# 03_-_AMG.net
KiCad netlist of a schematic drawn in Altium Designer
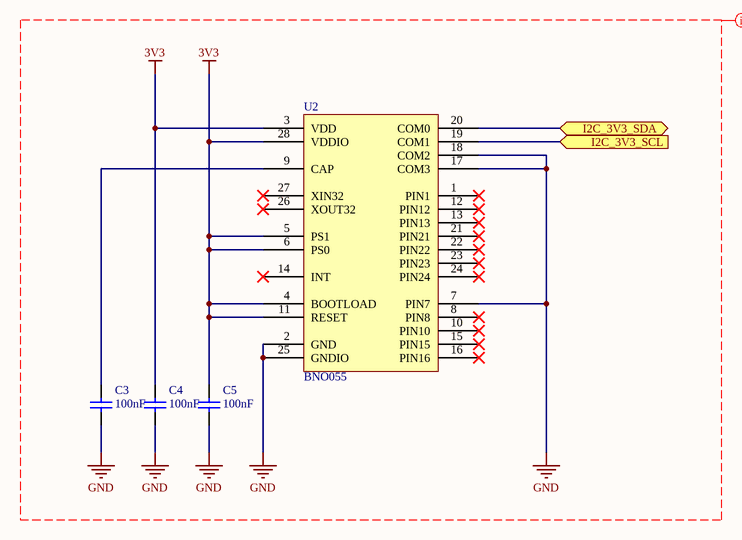
[diagram p0: [03] - AMG.SchDoc]

(export (version "E")
  (design (tool "Eeschema 10.0.6"))
  (components
    (comp (ref "C3")
      (value "100nF")
      (footprint "CAPC0603(1608)100_L")
      (description "CAP 100nF 50V ±10% 0603 (1608 Metric) Thickness 1mm SMD")
      (fields
        (field (name "TOLERANCE") "±10%")
        (field (name "MANUFACTURER PART NUMBER") "C0603C104K5RACAUTO")
      )
      (libsource (lib "Altium Content Vault") (part "CMP-1035-02592-1"))
    )
    (comp (ref "C4")
      (value "100nF")
      (footprint "CAPC0603(1608)100_L")
      (description "CAP 100nF 50V ±10% 0603 (1608 Metric) Thickness 1mm SMD")
      (fields
        (field (name "TOLERANCE") "±10%")
        (field (name "MANUFACTURER PART NUMBER") "C0603C104K5RACAUTO")
      )
      (libsource (lib "Altium Content Vault") (part "CMP-1035-02592-1"))
    )
    (comp (ref "C5")
      (value "100nF")
      (footprint "CAPC0603(1608)100_L")
      (description "CAP 100nF 50V ±10% 0603 (1608 Metric) Thickness 1mm SMD")
      (fields
        (field (name "TOLERANCE") "±10%")
        (field (name "MANUFACTURER PART NUMBER") "C0603C104K5RACAUTO")
      )
      (libsource (lib "Altium Content Vault") (part "CMP-1035-02592-1"))
    )
    (comp (ref "U2") (value "BNO055") (footprint "BNO055") (libsource (lib "BNO055") (part "BNO055")))
  )
  (nets
    (net (code "1") (name "/I2C_3V3_SCL") (class "Default")
      (node (ref "U2") (pin "19") (pinfunction "COM1_19") (pintype "passive"))
    )
    (net (code "2") (name "/I2C_3V3_SDA") (class "Default")
      (node (ref "U2") (pin "20") (pinfunction "COM0_20") (pintype "passive"))
    )
    (net (code "3") (name "3V3") (class "Default")
      (node (ref "C4") (pin "2") (pinfunction "2_2") (pintype "passive"))
      (node (ref "C5") (pin "2") (pinfunction "2_2") (pintype "passive"))
      (node (ref "U2") (pin "11") (pinfunction "RESET_11") (pintype "passive"))
      (node (ref "U2") (pin "28") (pinfunction "VDDIO_28") (pintype "passive"))
      (node (ref "U2") (pin "3") (pinfunction "VDD_3") (pintype "passive"))
      (node (ref "U2") (pin "4") (pinfunction "BOOTLOAD_4") (pintype "passive"))
      (node (ref "U2") (pin "5") (pinfunction "PS1_5") (pintype "passive"))
      (node (ref "U2") (pin "6") (pinfunction "PS0_6") (pintype "passive"))
    )
    (net (code "4") (name "GND") (class "Default")
      (node (ref "C3") (pin "1") (pinfunction "1_1") (pintype "passive"))
      (node (ref "C4") (pin "1") (pinfunction "1_1") (pintype "passive"))
      (node (ref "C5") (pin "1") (pinfunction "1_1") (pintype "passive"))
      (node (ref "U2") (pin "17") (pinfunction "COM3_17") (pintype "passive"))
      (node (ref "U2") (pin "18") (pinfunction "COM2_18") (pintype "passive"))
      (node (ref "U2") (pin "2") (pinfunction "GND_2") (pintype "passive"))
      (node (ref "U2") (pin "25") (pinfunction "GNDIO_25") (pintype "passive"))
      (node (ref "U2") (pin "7") (pinfunction "PIN7_7") (pintype "passive"))
    )
    (net (code "5") (name "Net-(U2-CAP)") (class "Default")
      (node (ref "C3") (pin "2") (pinfunction "2_2") (pintype "passive"))
      (node (ref "U2") (pin "9") (pinfunction "CAP_9") (pintype "passive"))
    )
    (net (code "6") (name "unconnected-(U2-INT-Pad14)") (class "Default")
      (node (ref "U2") (pin "14") (pinfunction "INT_14") (pintype "passive+no_connect"))
    )
    (net (code "7") (name "unconnected-(U2-PIN1-Pad1)") (class "Default")
      (node (ref "U2") (pin "1") (pinfunction "PIN1_1") (pintype "passive+no_connect"))
    )
    (net (code "8") (name "unconnected-(U2-PIN8-Pad8)") (class "Default")
      (node (ref "U2") (pin "8") (pinfunction "PIN8_8") (pintype "passive+no_connect"))
    )
    (net (code "9") (name "unconnected-(U2-PIN10-Pad10)") (class "Default")
      (node (ref "U2") (pin "10") (pinfunction "PIN10_10") (pintype "passive+no_connect"))
    )
    (net (code "10") (name "unconnected-(U2-PIN12-Pad12)") (class "Default")
      (node (ref "U2") (pin "12") (pinfunction "PIN12_12") (pintype "passive+no_connect"))
    )
    (net (code "11") (name "unconnected-(U2-PIN13-Pad13)") (class "Default")
      (node (ref "U2") (pin "13") (pinfunction "PIN13_13") (pintype "passive+no_connect"))
    )
    (net (code "12") (name "unconnected-(U2-PIN15-Pad15)") (class "Default")
      (node (ref "U2") (pin "15") (pinfunction "PIN15_15") (pintype "passive+no_connect"))
    )
    (net (code "13") (name "unconnected-(U2-PIN16-Pad16)") (class "Default")
      (node (ref "U2") (pin "16") (pinfunction "PIN16_16") (pintype "passive+no_connect"))
    )
    (net (code "14") (name "unconnected-(U2-PIN21-Pad21)") (class "Default")
      (node (ref "U2") (pin "21") (pinfunction "PIN21_21") (pintype "passive+no_connect"))
    )
    (net (code "15") (name "unconnected-(U2-PIN22-Pad22)") (class "Default")
      (node (ref "U2") (pin "22") (pinfunction "PIN22_22") (pintype "passive+no_connect"))
    )
    (net (code "16") (name "unconnected-(U2-PIN23-Pad23)") (class "Default")
      (node (ref "U2") (pin "23") (pinfunction "PIN23_23") (pintype "passive+no_connect"))
    )
    (net (code "17") (name "unconnected-(U2-PIN24-Pad24)") (class "Default")
      (node (ref "U2") (pin "24") (pinfunction "PIN24_24") (pintype "passive+no_connect"))
    )
    (net (code "18") (name "unconnected-(U2-XIN32-Pad27)") (class "Default")
      (node (ref "U2") (pin "27") (pinfunction "XIN32_27") (pintype "passive+no_connect"))
    )
    (net (code "19") (name "unconnected-(U2-XOUT32-Pad26)") (class "Default")
      (node (ref "U2") (pin "26") (pinfunction "XOUT32_26") (pintype "passive+no_connect"))
    )
  )
)
